# stamp-fixed-mk2.net
KiCad netlist of a schematic drawn in EAGLE
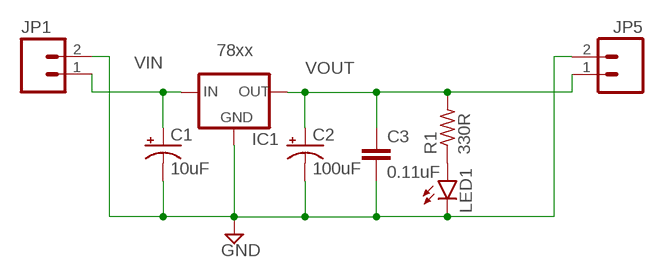
[diagram p0: schematic, sheet 1]

(export (version "E")
  (design (tool "Eeschema 10.0.6"))
  (components
    (comp (ref "C1")
      (value "10uF")
      (footprint "eagle-import:E2,5-6")
      (libsource (lib "eagle-import") (part "CAPACITOR-POLARIZEDE2.5-6"))
    )
    (comp (ref "C2")
      (value "100uF")
      (footprint "eagle-import:E2,5-6")
      (libsource (lib "eagle-import") (part "CAPACITOR-POLARIZEDE2.5-6"))
    )
    (comp (ref "C3")
      (value "0.11uF")
      (footprint "eagle-import:C025-024X044")
      (libsource (lib "eagle-import") (part "CAPACITOR-CERAMIC025-024X044"))
    )
    (comp (ref "IC1")
      (value "78xx")
      (footprint "eagle-import:TO-220-SIDE-THERM")
      (libsource (lib "eagle-import") (part "V_REG_78XXTO-220-THERM"))
    )
    (comp (ref "JP1")
      (value "M02JST-PTH-2")
      (footprint "eagle-import:JST-2-PTH")
      (libsource (lib "eagle-import") (part "M02JST-PTH-2"))
    )
    (comp (ref "JP5")
      (value "M02JST-PTH-2")
      (footprint "eagle-import:JST-2-PTH")
      (libsource (lib "eagle-import") (part "M02JST-PTH-2"))
    )
    (comp (ref "LED1")
      (value "LED3MM")
      (footprint "eagle-import:LED3MM")
      (libsource (lib "eagle-import") (part "LED3MM"))
    )
    (comp (ref "R1")
      (value "330R")
      (footprint "eagle-import:RESISTOR-AXIAL-PTH-5.08MM")
      (libsource (lib "eagle-import") (part "RESISTORPTH-AXIAL-5.08MM"))
    )
  )
  (nets
    (net (code "1") (name "/VIN") (class "Default")
      (node (ref "C1") (pin "+") (pinfunction "+_+") (pintype "passive"))
      (node (ref "IC1") (pin "IN") (pinfunction "IN_IN") (pintype "input"))
      (node (ref "JP1") (pin "1") (pinfunction "1_1") (pintype "passive"))
    )
    (net (code "2") (name "/VOUT") (class "Default")
      (node (ref "C2") (pin "+") (pinfunction "+_+") (pintype "passive"))
      (node (ref "C3") (pin "1") (pinfunction "1_1") (pintype "passive"))
      (node (ref "IC1") (pin "OUT") (pinfunction "OUT_OUT") (pintype "output"))
      (node (ref "JP5") (pin "1") (pinfunction "1_1") (pintype "passive"))
      (node (ref "R1") (pin "P$2") (pinfunction "2_P$2") (pintype "passive"))
    )
    (net (code "3") (name "GND") (class "Default")
      (node (ref "C1") (pin "-") (pinfunction "-_-") (pintype "passive"))
      (node (ref "C2") (pin "-") (pinfunction "-_-") (pintype "passive"))
      (node (ref "C3") (pin "2") (pinfunction "2_2") (pintype "passive"))
      (node (ref "IC1") (pin "GND") (pinfunction "GND_GND") (pintype "input"))
      (node (ref "IC1") (pin "GND@1") (pinfunction "GND_GND@1") (pintype "input"))
      (node (ref "IC1") (pin "GND@10") (pinfunction "GND_GND@10") (pintype "input"))
      (node (ref "IC1") (pin "GND@11") (pinfunction "GND_GND@11") (pintype "input"))
      (node (ref "IC1") (pin "GND@12") (pinfunction "GND_GND@12") (pintype "input"))
      (node (ref "IC1") (pin "GND@13") (pinfunction "GND_GND@13") (pintype "input"))
      (node (ref "IC1") (pin "GND@14") (pinfunction "GND_GND@14") (pintype "input"))
      (node (ref "IC1") (pin "GND@15") (pinfunction "GND_GND@15") (pintype "input"))
      (node (ref "IC1") (pin "GND@16") (pinfunction "GND_GND@16") (pintype "input"))
      (node (ref "IC1") (pin "GND@17") (pinfunction "GND_GND@17") (pintype "input"))
      (node (ref "IC1") (pin "GND@18") (pinfunction "GND_GND@18") (pintype "input"))
      (node (ref "IC1") (pin "GND@19") (pinfunction "GND_GND@19") (pintype "input"))
      (node (ref "IC1") (pin "GND@2") (pinfunction "GND_GND@2") (pintype "input"))
      (node (ref "IC1") (pin "GND@20") (pinfunction "GND_GND@20") (pintype "input"))
      (node (ref "IC1") (pin "GND@21") (pinfunction "GND_GND@21") (pintype "input"))
      (node (ref "IC1") (pin "GND@22") (pinfunction "GND_GND@22") (pintype "input"))
      (node (ref "IC1") (pin "GND@23") (pinfunction "GND_GND@23") (pintype "input"))
      (node (ref "IC1") (pin "GND@24") (pinfunction "GND_GND@24") (pintype "input"))
      (node (ref "IC1") (pin "GND@25") (pinfunction "GND_GND@25") (pintype "input"))
      (node (ref "IC1") (pin "GND@26") (pinfunction "GND_GND@26") (pintype "input"))
      (node (ref "IC1") (pin "GND@27") (pinfunction "GND_GND@27") (pintype "input"))
      (node (ref "IC1") (pin "GND@3") (pinfunction "GND_GND@3") (pintype "input"))
      (node (ref "IC1") (pin "GND@4") (pinfunction "GND_GND@4") (pintype "input"))
      (node (ref "IC1") (pin "GND@5") (pinfunction "GND_GND@5") (pintype "input"))
      (node (ref "IC1") (pin "GND@6") (pinfunction "GND_GND@6") (pintype "input"))
      (node (ref "IC1") (pin "GND@7") (pinfunction "GND_GND@7") (pintype "input"))
      (node (ref "IC1") (pin "GND@8") (pinfunction "GND_GND@8") (pintype "input"))
      (node (ref "IC1") (pin "GND@9") (pinfunction "GND_GND@9") (pintype "input"))
      (node (ref "JP1") (pin "2") (pinfunction "2_2") (pintype "passive"))
      (node (ref "JP5") (pin "2") (pinfunction "2_2") (pintype "passive"))
      (node (ref "LED1") (pin "K") (pinfunction "C_K") (pintype "passive"))
    )
    (net (code "4") (name "Net-(R1-1)") (class "Default")
      (node (ref "LED1") (pin "A") (pinfunction "A_A") (pintype "passive"))
      (node (ref "R1") (pin "P$1") (pinfunction "1_P$1") (pintype "passive"))
    )
  )
)
